# FRA_breakout6U_v1.net
KiCad netlist of a schematic drawn in EAGLE
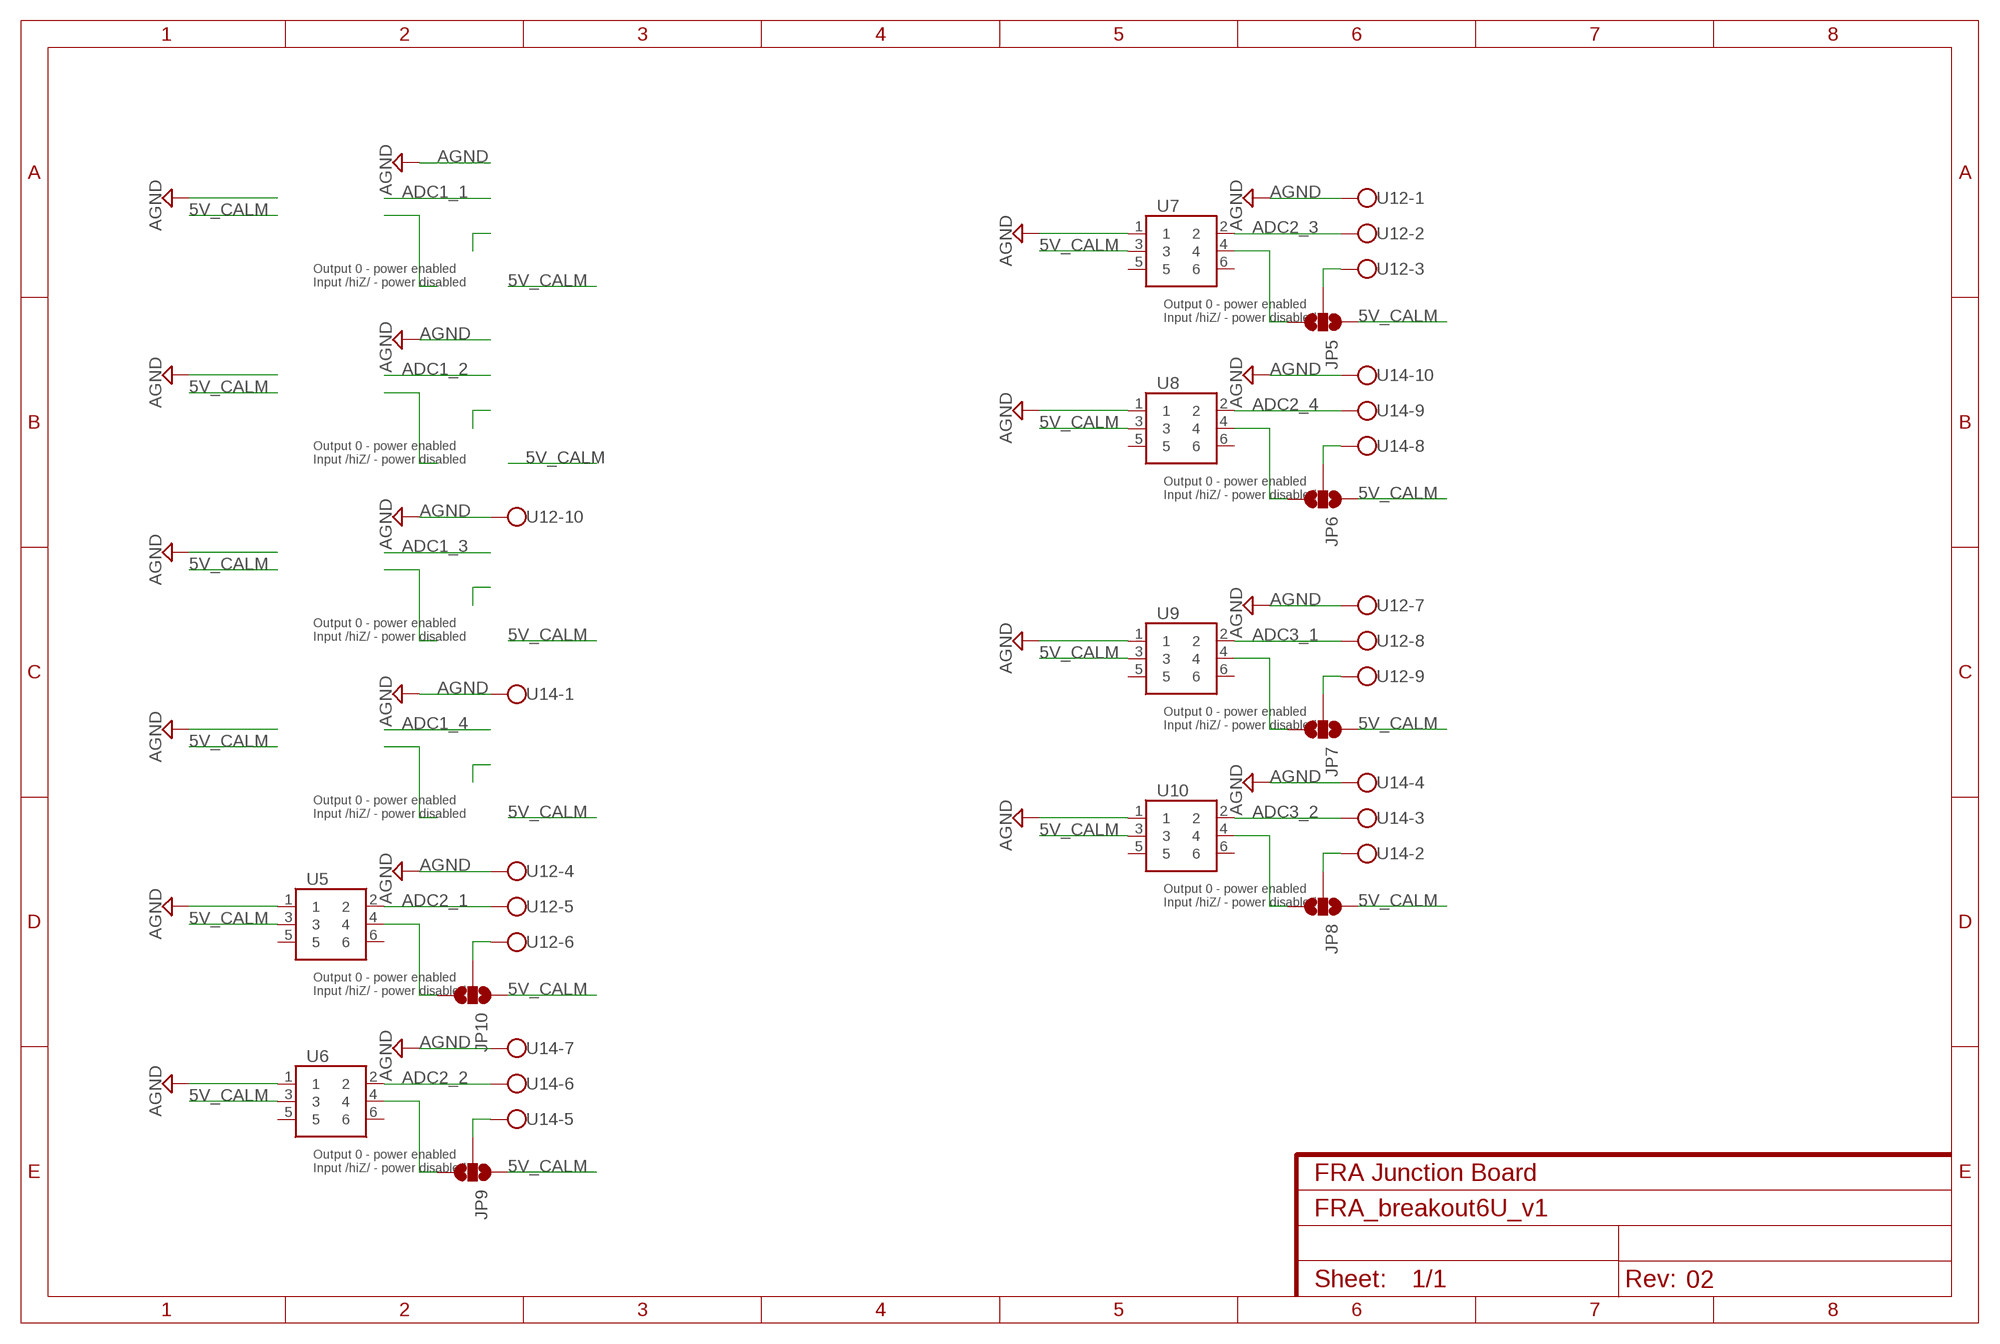
[diagram p0: schematic, sheet 1]

(export (version "E")
  (design (tool "Eeschema 10.0.6"))
  (components
    (comp (ref "JP5")
      (value "JUMPER-SMT_3_NO_NO_SILK")
      (footprint "eagle-import:SMT-JUMPER_3_0-NO_TRACE_NO-SILK")
      (libsource (lib "eagle-import") (part "JUMPER-SMT_3_NO_NO_SILK"))
    )
    (comp (ref "JP6")
      (value "JUMPER-SMT_3_NO_NO_SILK")
      (footprint "eagle-import:SMT-JUMPER_3_0-NO_TRACE_NO-SILK")
      (libsource (lib "eagle-import") (part "JUMPER-SMT_3_NO_NO_SILK"))
    )
    (comp (ref "JP7")
      (value "JUMPER-SMT_3_NO_NO_SILK")
      (footprint "eagle-import:SMT-JUMPER_3_0-NO_TRACE_NO-SILK")
      (libsource (lib "eagle-import") (part "JUMPER-SMT_3_NO_NO_SILK"))
    )
    (comp (ref "JP8")
      (value "JUMPER-SMT_3_NO_NO_SILK")
      (footprint "eagle-import:SMT-JUMPER_3_0-NO_TRACE_NO-SILK")
      (libsource (lib "eagle-import") (part "JUMPER-SMT_3_NO_NO_SILK"))
    )
    (comp (ref "JP9")
      (value "JUMPER-SMT_3_NO_NO_SILK")
      (footprint "eagle-import:SMT-JUMPER_3_0-NO_TRACE_NO-SILK")
      (libsource (lib "eagle-import") (part "JUMPER-SMT_3_NO_NO_SILK"))
    )
    (comp (ref "JP10")
      (value "JUMPER-SMT_3_NO_NO_SILK")
      (footprint "eagle-import:SMT-JUMPER_3_0-NO_TRACE_NO-SILK")
      (libsource (lib "eagle-import") (part "JUMPER-SMT_3_NO_NO_SILK"))
    )
    (comp (ref "U5")
      (value "SSW-103-01-F-D")
      (footprint "eagle-import:SHDR6W79P254_2X3_813X495X851P")
      (fields (field (name "MOUSER_PART_NUMBER") "200-SSW10301FD") (field (name "PARTNO") "61200621621"))
      (libsource (lib "eagle-import") (part "SSW-103-01-F-D"))
    )
    (comp (ref "U6")
      (value "SSW-103-01-F-D")
      (footprint "eagle-import:SHDR6W79P254_2X3_813X495X851P")
      (fields (field (name "MOUSER_PART_NUMBER") "200-SSW10301FD") (field (name "PARTNO") "61200621621"))
      (libsource (lib "eagle-import") (part "SSW-103-01-F-D"))
    )
    (comp (ref "U7")
      (value "SSW-103-01-F-D")
      (footprint "eagle-import:SHDR6W79P254_2X3_813X495X851P")
      (fields (field (name "MOUSER_PART_NUMBER") "200-SSW10301FD") (field (name "PARTNO") "61200621621"))
      (libsource (lib "eagle-import") (part "SSW-103-01-F-D"))
    )
    (comp (ref "U8")
      (value "SSW-103-01-F-D")
      (footprint "eagle-import:SHDR6W79P254_2X3_813X495X851P")
      (fields (field (name "MOUSER_PART_NUMBER") "200-SSW10301FD") (field (name "PARTNO") "61200621621"))
      (libsource (lib "eagle-import") (part "SSW-103-01-F-D"))
    )
    (comp (ref "U9")
      (value "SSW-103-01-F-D")
      (footprint "eagle-import:SHDR6W79P254_2X3_813X495X851P")
      (fields (field (name "MOUSER_PART_NUMBER") "200-SSW10301FD") (field (name "PARTNO") "61200621621"))
      (libsource (lib "eagle-import") (part "SSW-103-01-F-D"))
    )
    (comp (ref "U10")
      (value "SSW-103-01-F-D")
      (footprint "eagle-import:SHDR6W79P254_2X3_813X495X851P")
      (fields (field (name "MOUSER_PART_NUMBER") "200-SSW10301FD") (field (name "PARTNO") "61200621621"))
      (libsource (lib "eagle-import") (part "SSW-103-01-F-D"))
    )
    (comp (ref "U12")
      (value "TB003V-500-P10BE")
      (footprint "eagle-import:TB003V-500-P10BE")
      (libsource (lib "eagle-import") (part "TB003V-500-P10BE"))
    )
    (comp (ref "U14")
      (value "TB003V-500-P10BE")
      (footprint "eagle-import:TB003V-500-P10BE")
      (libsource (lib "eagle-import") (part "TB003V-500-P10BE"))
    )
  )
  (nets
    (net (code "1") (name "/5V_CALM") (class "Default")
      (node (ref "JP10") (pin "1") (pinfunction "1_1") (pintype "passive"))
      (node (ref "JP5") (pin "1") (pinfunction "1_1") (pintype "passive"))
      (node (ref "JP6") (pin "1") (pinfunction "1_1") (pintype "passive"))
      (node (ref "JP7") (pin "1") (pinfunction "1_1") (pintype "passive"))
      (node (ref "JP8") (pin "1") (pinfunction "1_1") (pintype "passive"))
      (node (ref "JP9") (pin "1") (pinfunction "1_1") (pintype "passive"))
      (node (ref "U10") (pin "3") (pinfunction "3_3") (pintype "bidirectional"))
      (node (ref "U5") (pin "3") (pinfunction "3_3") (pintype "bidirectional"))
      (node (ref "U6") (pin "3") (pinfunction "3_3") (pintype "bidirectional"))
      (node (ref "U7") (pin "3") (pinfunction "3_3") (pintype "bidirectional"))
      (node (ref "U8") (pin "3") (pinfunction "3_3") (pintype "bidirectional"))
      (node (ref "U9") (pin "3") (pinfunction "3_3") (pintype "bidirectional"))
    )
    (net (code "6") (name "/ADC2_1") (class "Default")
      (node (ref "U12") (pin "5") (pinfunction "KL_5") (pintype "passive"))
      (node (ref "U5") (pin "2") (pinfunction "2_2") (pintype "bidirectional"))
    )
    (net (code "7") (name "/ADC2_2") (class "Default")
      (node (ref "U14") (pin "6") (pinfunction "KL_6") (pintype "passive"))
      (node (ref "U6") (pin "2") (pinfunction "2_2") (pintype "bidirectional"))
    )
    (net (code "8") (name "/ADC2_3") (class "Default")
      (node (ref "U12") (pin "2") (pinfunction "KL_2") (pintype "passive"))
      (node (ref "U7") (pin "2") (pinfunction "2_2") (pintype "bidirectional"))
    )
    (net (code "9") (name "/ADC2_4") (class "Default")
      (node (ref "U14") (pin "9") (pinfunction "KL_9") (pintype "passive"))
      (node (ref "U8") (pin "2") (pinfunction "2_2") (pintype "bidirectional"))
    )
    (net (code "10") (name "/ADC3_1") (class "Default")
      (node (ref "U12") (pin "8") (pinfunction "KL_8") (pintype "passive"))
      (node (ref "U9") (pin "2") (pinfunction "2_2") (pintype "bidirectional"))
    )
    (net (code "11") (name "/ADC3_2") (class "Default")
      (node (ref "U10") (pin "2") (pinfunction "2_2") (pintype "bidirectional"))
      (node (ref "U14") (pin "3") (pinfunction "KL_3") (pintype "passive"))
    )
    (net (code "12") (name "AGND") (class "Default")
      (node (ref "U10") (pin "1") (pinfunction "1_1") (pintype "bidirectional"))
      (node (ref "U12") (pin "1") (pinfunction "KL_1") (pintype "passive"))
      (node (ref "U12") (pin "10") (pinfunction "KL_10") (pintype "passive"))
      (node (ref "U12") (pin "4") (pinfunction "KL_4") (pintype "passive"))
      (node (ref "U12") (pin "7") (pinfunction "KL_7") (pintype "passive"))
      (node (ref "U14") (pin "1") (pinfunction "KL_1") (pintype "passive"))
      (node (ref "U14") (pin "10") (pinfunction "KL_10") (pintype "passive"))
      (node (ref "U14") (pin "4") (pinfunction "KL_4") (pintype "passive"))
      (node (ref "U14") (pin "7") (pinfunction "KL_7") (pintype "passive"))
      (node (ref "U5") (pin "1") (pinfunction "1_1") (pintype "bidirectional"))
      (node (ref "U6") (pin "1") (pinfunction "1_1") (pintype "bidirectional"))
      (node (ref "U7") (pin "1") (pinfunction "1_1") (pintype "bidirectional"))
      (node (ref "U8") (pin "1") (pinfunction "1_1") (pintype "bidirectional"))
      (node (ref "U9") (pin "1") (pinfunction "1_1") (pintype "bidirectional"))
    )
    (net (code "13") (name "Net-(JP5-Pad3)") (class "Default")
      (node (ref "JP5") (pin "3") (pinfunction "3_3") (pintype "passive"))
      (node (ref "U7") (pin "4") (pinfunction "4_4") (pintype "bidirectional"))
    )
    (net (code "14") (name "Net-(JP6-Pad3)") (class "Default")
      (node (ref "JP6") (pin "3") (pinfunction "3_3") (pintype "passive"))
      (node (ref "U8") (pin "4") (pinfunction "4_4") (pintype "bidirectional"))
    )
    (net (code "15") (name "Net-(JP7-Pad3)") (class "Default")
      (node (ref "JP7") (pin "3") (pinfunction "3_3") (pintype "passive"))
      (node (ref "U9") (pin "4") (pinfunction "4_4") (pintype "bidirectional"))
    )
    (net (code "16") (name "Net-(JP8-Pad3)") (class "Default")
      (node (ref "JP8") (pin "3") (pinfunction "3_3") (pintype "passive"))
      (node (ref "U10") (pin "4") (pinfunction "4_4") (pintype "bidirectional"))
    )
    (net (code "17") (name "Net-(JP9-Pad3)") (class "Default")
      (node (ref "JP9") (pin "3") (pinfunction "3_3") (pintype "passive"))
      (node (ref "U6") (pin "4") (pinfunction "4_4") (pintype "bidirectional"))
    )
    (net (code "18") (name "Net-(JP10-Pad3)") (class "Default")
      (node (ref "JP10") (pin "3") (pinfunction "3_3") (pintype "passive"))
      (node (ref "U5") (pin "4") (pinfunction "4_4") (pintype "bidirectional"))
    )
    (net (code "19") (name "Net-(U12D-KL)") (class "Default")
      (node (ref "JP5") (pin "2") (pinfunction "2_2") (pintype "passive"))
      (node (ref "U12") (pin "3") (pinfunction "KL_3") (pintype "passive"))
    )
    (net (code "20") (name "Net-(U12G-KL)") (class "Default")
      (node (ref "JP10") (pin "2") (pinfunction "2_2") (pintype "passive"))
      (node (ref "U12") (pin "6") (pinfunction "KL_6") (pintype "passive"))
    )
    (net (code "21") (name "Net-(U12J-KL)") (class "Default")
      (node (ref "JP7") (pin "2") (pinfunction "2_2") (pintype "passive"))
      (node (ref "U12") (pin "9") (pinfunction "KL_9") (pintype "passive"))
    )
    (net (code "22") (name "Net-(U14C-KL)") (class "Default")
      (node (ref "JP8") (pin "2") (pinfunction "2_2") (pintype "passive"))
      (node (ref "U14") (pin "2") (pinfunction "KL_2") (pintype "passive"))
    )
    (net (code "23") (name "Net-(U14F-KL)") (class "Default")
      (node (ref "JP9") (pin "2") (pinfunction "2_2") (pintype "passive"))
      (node (ref "U14") (pin "5") (pinfunction "KL_5") (pintype "passive"))
    )
    (net (code "24") (name "Net-(U14I-KL)") (class "Default")
      (node (ref "JP6") (pin "2") (pinfunction "2_2") (pintype "passive"))
      (node (ref "U14") (pin "8") (pinfunction "KL_8") (pintype "passive"))
    )
    (net (code "25") (name "unconnected-(U5-Pad5)") (class "Default")
      (node (ref "U5") (pin "5") (pinfunction "5_5") (pintype "bidirectional"))
    )
    (net (code "26") (name "unconnected-(U5-Pad6)") (class "Default")
      (node (ref "U5") (pin "6") (pinfunction "6_6") (pintype "bidirectional"))
    )
    (net (code "27") (name "unconnected-(U6-Pad5)") (class "Default")
      (node (ref "U6") (pin "5") (pinfunction "5_5") (pintype "bidirectional"))
    )
    (net (code "28") (name "unconnected-(U6-Pad6)") (class "Default")
      (node (ref "U6") (pin "6") (pinfunction "6_6") (pintype "bidirectional"))
    )
    (net (code "29") (name "unconnected-(U7-Pad5)") (class "Default")
      (node (ref "U7") (pin "5") (pinfunction "5_5") (pintype "bidirectional"))
    )
    (net (code "30") (name "unconnected-(U7-Pad6)") (class "Default")
      (node (ref "U7") (pin "6") (pinfunction "6_6") (pintype "bidirectional"))
    )
    (net (code "31") (name "unconnected-(U8-Pad5)") (class "Default")
      (node (ref "U8") (pin "5") (pinfunction "5_5") (pintype "bidirectional"))
    )
    (net (code "32") (name "unconnected-(U8-Pad6)") (class "Default")
      (node (ref "U8") (pin "6") (pinfunction "6_6") (pintype "bidirectional"))
    )
    (net (code "33") (name "unconnected-(U9-Pad5)") (class "Default")
      (node (ref "U9") (pin "5") (pinfunction "5_5") (pintype "bidirectional"))
    )
    (net (code "34") (name "unconnected-(U9-Pad6)") (class "Default")
      (node (ref "U9") (pin "6") (pinfunction "6_6") (pintype "bidirectional"))
    )
    (net (code "35") (name "unconnected-(U10-Pad5)") (class "Default")
      (node (ref "U10") (pin "5") (pinfunction "5_5") (pintype "bidirectional"))
    )
    (net (code "36") (name "unconnected-(U10-Pad6)") (class "Default")
      (node (ref "U10") (pin "6") (pinfunction "6_6") (pintype "bidirectional"))
    )
  )
)
